# M307A.net
KiCad netlist of a schematic drawn in EAGLE
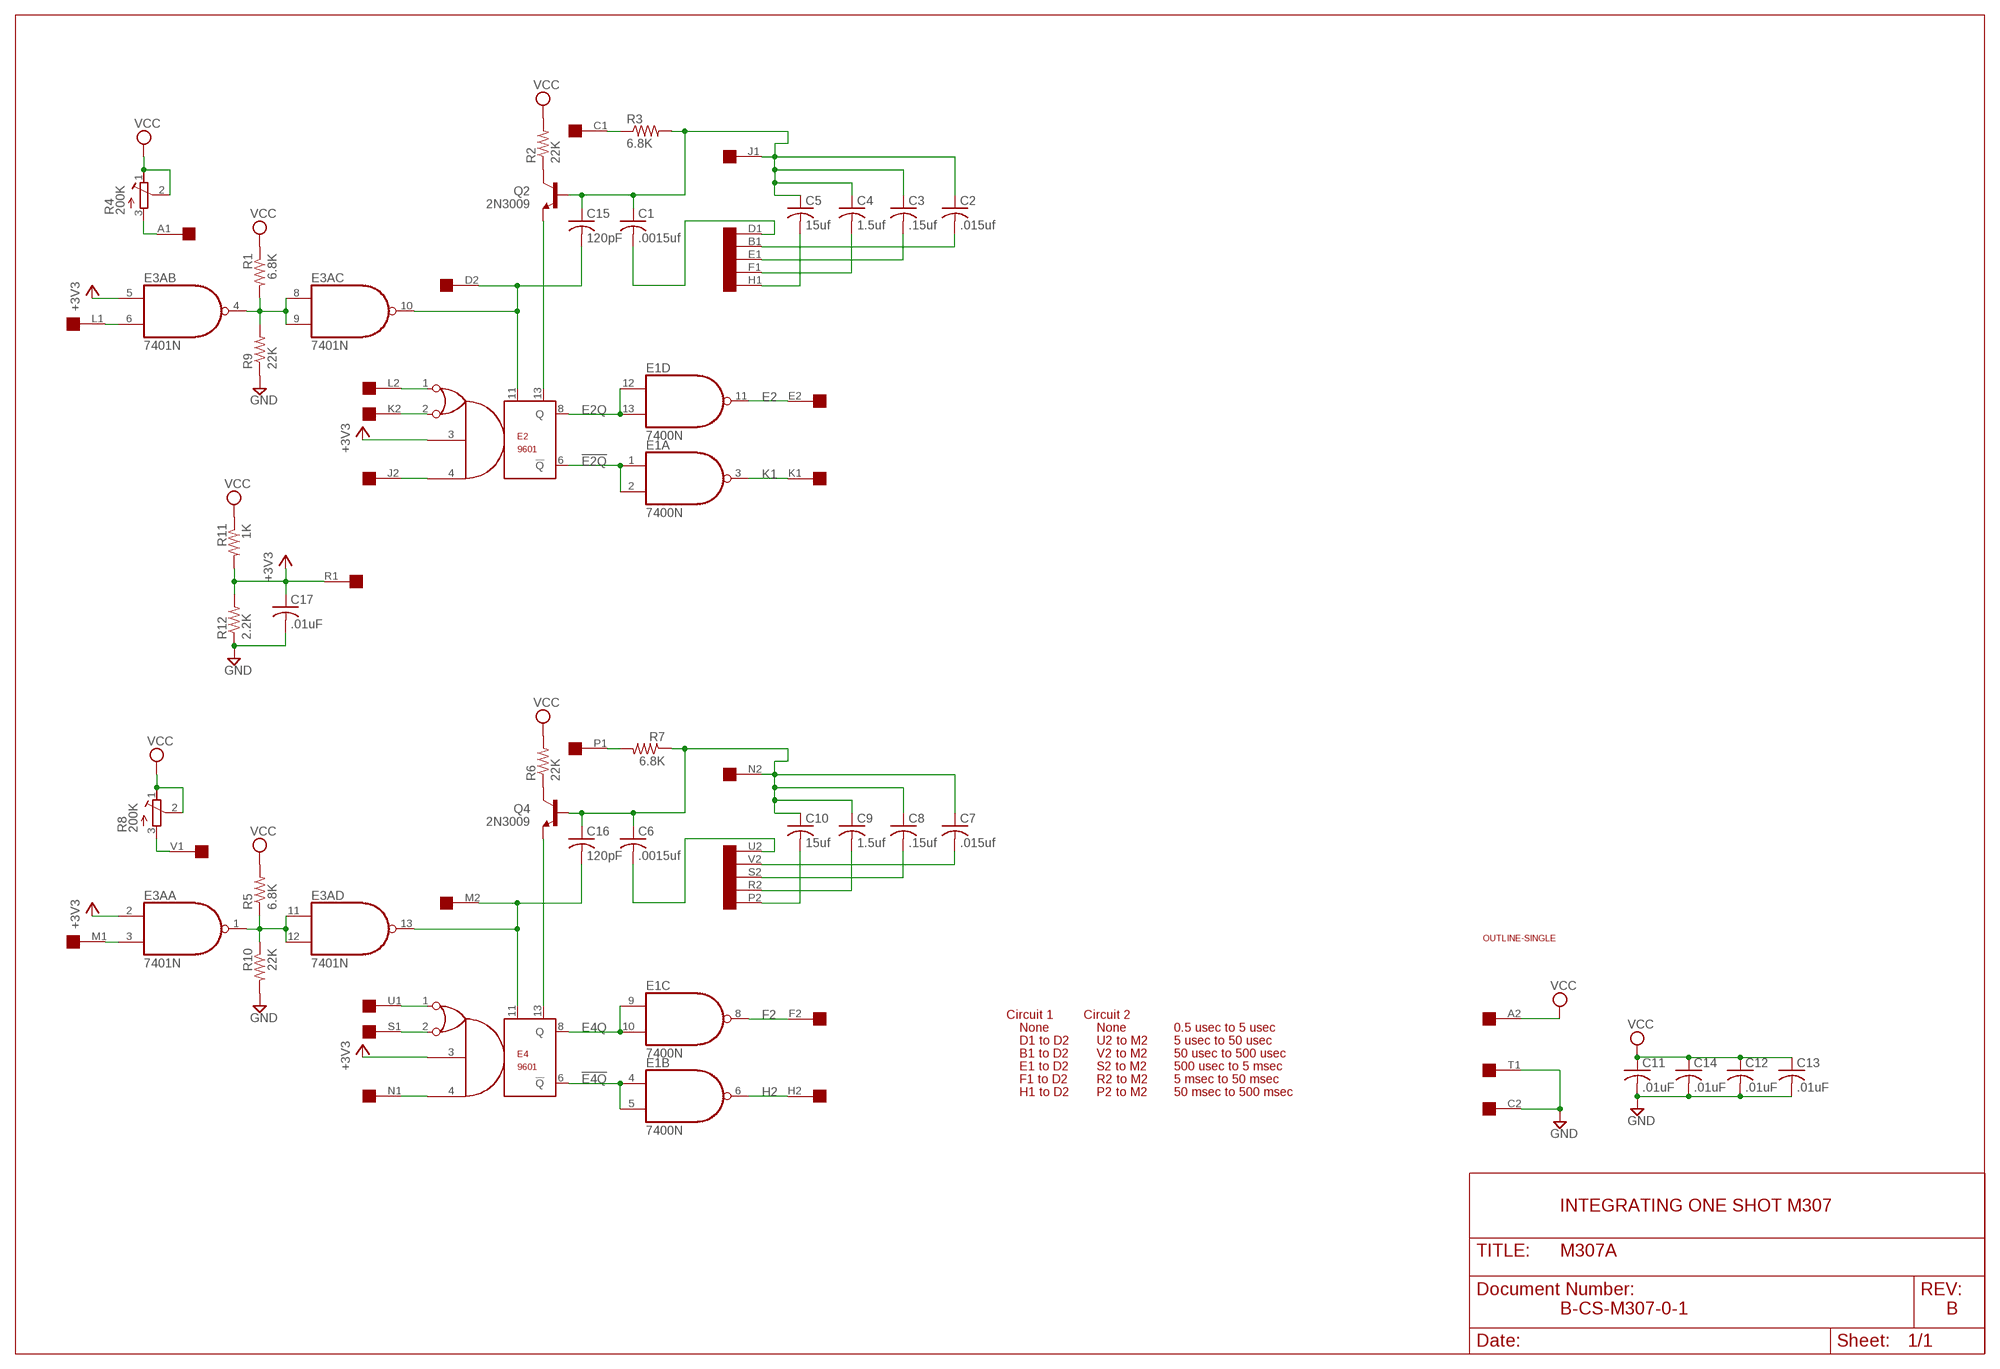
[diagram p0: schematic, sheet 1]

(export (version "E")
  (design (tool "Eeschema 10.0.6"))
  (components
    (comp (ref "C1")
      (value ".0015uf")
      (footprint "eagle-import:C050-025X075")
      (libsource (lib "eagle-import") (part "C-US050-025X075"))
    )
    (comp (ref "C2")
      (value ".015uf")
      (footprint "eagle-import:C150-054X183")
      (libsource (lib "eagle-import") (part "C-US150-054X183"))
    )
    (comp (ref "C3")
      (value ".15uf")
      (footprint "eagle-import:C102-054X133")
      (libsource (lib "eagle-import") (part "C-US102-054X133"))
    )
    (comp (ref "C4")
      (value "1.5uf")
      (footprint "eagle-import:C150-054X183")
      (libsource (lib "eagle-import") (part "C-US150-054X183"))
    )
    (comp (ref "C5")
      (value "15uf")
      (footprint "eagle-import:C150-054X183")
      (libsource (lib "eagle-import") (part "C-US150-054X183"))
    )
    (comp (ref "C6")
      (value ".0015uf")
      (footprint "eagle-import:C050-025X075")
      (libsource (lib "eagle-import") (part "C-US050-025X075"))
    )
    (comp (ref "C7")
      (value ".015uf")
      (footprint "eagle-import:C150-054X183")
      (libsource (lib "eagle-import") (part "C-US150-054X183"))
    )
    (comp (ref "C8")
      (value ".15uf")
      (footprint "eagle-import:C102-054X133")
      (libsource (lib "eagle-import") (part "C-US102-054X133"))
    )
    (comp (ref "C9")
      (value "1.5uf")
      (footprint "eagle-import:C150-054X183")
      (libsource (lib "eagle-import") (part "C-US150-054X183"))
    )
    (comp (ref "C10")
      (value "15uf")
      (footprint "eagle-import:C150-054X183")
      (libsource (lib "eagle-import") (part "C-US150-054X183"))
    )
    (comp (ref "C11")
      (value ".01uF")
      (footprint "eagle-import:C050-025X075")
      (libsource (lib "eagle-import") (part "C-US050-025X075"))
    )
    (comp (ref "C12")
      (value ".01uF")
      (footprint "eagle-import:C050-025X075")
      (libsource (lib "eagle-import") (part "C-US050-025X075"))
    )
    (comp (ref "C13")
      (value ".01uF")
      (footprint "eagle-import:C050-025X075")
      (libsource (lib "eagle-import") (part "C-US050-025X075"))
    )
    (comp (ref "C14")
      (value ".01uF")
      (footprint "eagle-import:C050-025X075")
      (libsource (lib "eagle-import") (part "C-US050-025X075"))
    )
    (comp (ref "C15")
      (value "120pF")
      (footprint "eagle-import:C050-025X075")
      (libsource (lib "eagle-import") (part "C-US050-025X075"))
    )
    (comp (ref "C16")
      (value "120pF")
      (footprint "eagle-import:C050-025X075")
      (libsource (lib "eagle-import") (part "C-US050-025X075"))
    )
    (comp (ref "C17")
      (value ".01uF")
      (footprint "eagle-import:C050-025X075")
      (libsource (lib "eagle-import") (part "C-US050-025X075"))
    )
    (comp (ref "E1")
      (value "7400N")
      (footprint "eagle-import:DIL14")
      (libsource (lib "eagle-import") (part "7400N"))
    )
    (comp (ref "E2")
      (value "9601")
      (footprint "eagle-import:DIL14")
      (libsource (lib "eagle-import") (part "9601"))
    )
    (comp (ref "E3A")
      (value "7401N")
      (footprint "eagle-import:DIL14")
      (libsource (lib "eagle-import") (part "7401NLS"))
    )
    (comp (ref "E4")
      (value "9601")
      (footprint "eagle-import:DIL14")
      (libsource (lib "eagle-import") (part "9601"))
    )
    (comp (ref "Q2")
      (value "2N3009")
      (footprint "eagle-import:TO39")
      (libsource (lib "eagle-import") (part "-NPN-TO39-EBC2N3019"))
    )
    (comp (ref "Q4")
      (value "2N3009")
      (footprint "eagle-import:TO39")
      (libsource (lib "eagle-import") (part "-NPN-TO39-EBC2N3019"))
    )
    (comp (ref "R1")
      (value "6.8K")
      (footprint "eagle-import:0207_10")
      (libsource (lib "eagle-import") (part "R-US_0207/10"))
    )
    (comp (ref "R2")
      (value "22K")
      (footprint "eagle-import:0207_10")
      (libsource (lib "eagle-import") (part "R-US_0207/10"))
    )
    (comp (ref "R3")
      (value "6.8K")
      (footprint "eagle-import:0207_10")
      (libsource (lib "eagle-import") (part "R-US_0207/10"))
    )
    (comp (ref "R4")
      (value "200K")
      (footprint "eagle-import:3006Y")
      (libsource (lib "eagle-import") (part "275P"))
    )
    (comp (ref "R5")
      (value "6.8K")
      (footprint "eagle-import:0207_10")
      (libsource (lib "eagle-import") (part "R-US_0207/10"))
    )
    (comp (ref "R6")
      (value "22K")
      (footprint "eagle-import:0207_10")
      (libsource (lib "eagle-import") (part "R-US_0207/10"))
    )
    (comp (ref "R7")
      (value "6.8K")
      (footprint "eagle-import:0207_10")
      (libsource (lib "eagle-import") (part "R-US_0207/10"))
    )
    (comp (ref "R8")
      (value "200K")
      (footprint "eagle-import:3006Y")
      (libsource (lib "eagle-import") (part "275P"))
    )
    (comp (ref "R9")
      (value "22K")
      (footprint "eagle-import:0207_10")
      (libsource (lib "eagle-import") (part "R-US_0207/10"))
    )
    (comp (ref "R10")
      (value "22K")
      (footprint "eagle-import:0207_10")
      (libsource (lib "eagle-import") (part "R-US_0207/10"))
    )
    (comp (ref "R11")
      (value "1K")
      (footprint "eagle-import:0207_10")
      (libsource (lib "eagle-import") (part "R-US_0207/10"))
    )
    (comp (ref "R12")
      (value "2.2K")
      (footprint "eagle-import:0207_10")
      (libsource (lib "eagle-import") (part "R-US_0207/10"))
    )
    (comp (ref "U$1")
      (value "OUTLINE-SINGLE")
      (footprint "eagle-import:SINGLE")
      (libsource (lib "eagle-import") (part "OUTLINE-SINGLE"))
    )
    (comp (ref "U$4")
      (value "SINGLE")
      (footprint "eagle-import:EDGE-CON2")
      (libsource (lib "eagle-import") (part "SINGLE"))
    )
  )
  (nets
    (net (code "1") (name "+3V3") (class "Default")
      (node (ref "C17") (pin "1") (pinfunction "1_1") (pintype "passive"))
      (node (ref "E2") (pin "3") (pinfunction "P$3_3") (pintype "input"))
      (node (ref "E3A") (pin "2") (pinfunction "I0_2") (pintype "input"))
      (node (ref "E3A") (pin "5") (pinfunction "I0_5") (pintype "input"))
      (node (ref "E4") (pin "3") (pinfunction "P$3_3") (pintype "input"))
      (node (ref "R11") (pin "2") (pinfunction "2_2") (pintype "passive"))
      (node (ref "R12") (pin "2") (pinfunction "2_2") (pintype "passive"))
      (node (ref "U$4") (pin "R1") (pinfunction "1_R1") (pintype "bidirectional"))
    )
    (net (code "2") (name "/E2") (class "Default")
      (node (ref "E1") (pin "11") (pinfunction "O_11") (pintype "output"))
      (node (ref "U$4") (pin "E2") (pinfunction "1_E2") (pintype "bidirectional"))
    )
    (net (code "3") (name "/E2Q") (class "Default")
      (node (ref "E1") (pin "12") (pinfunction "I0_12") (pintype "input"))
      (node (ref "E1") (pin "13") (pinfunction "I1_13") (pintype "input"))
      (node (ref "E2") (pin "8") (pinfunction "Q_8") (pintype "output"))
    )
    (net (code "4") (name "/E4Q") (class "Default")
      (node (ref "E1") (pin "10") (pinfunction "I1_10") (pintype "input"))
      (node (ref "E1") (pin "9") (pinfunction "I0_9") (pintype "input"))
      (node (ref "E4") (pin "8") (pinfunction "Q_8") (pintype "output"))
    )
    (net (code "5") (name "/F2") (class "Default")
      (node (ref "E1") (pin "8") (pinfunction "O_8") (pintype "output"))
      (node (ref "U$4") (pin "F2") (pinfunction "1_F2") (pintype "bidirectional"))
    )
    (net (code "6") (name "/H2") (class "Default")
      (node (ref "E1") (pin "6") (pinfunction "O_6") (pintype "output"))
      (node (ref "U$4") (pin "H2") (pinfunction "1_H2") (pintype "bidirectional"))
    )
    (net (code "7") (name "/K1") (class "Default")
      (node (ref "E1") (pin "3") (pinfunction "O_3") (pintype "output"))
      (node (ref "U$4") (pin "K1") (pinfunction "1_K1") (pintype "bidirectional"))
    )
    (net (code "8") (name "/~{E2Q}") (class "Default")
      (node (ref "E1") (pin "1") (pinfunction "I0_1") (pintype "input"))
      (node (ref "E1") (pin "2") (pinfunction "I1_2") (pintype "input"))
      (node (ref "E2") (pin "6") (pinfunction "~{Q}_6") (pintype "output"))
    )
    (net (code "9") (name "/~{E4Q}") (class "Default")
      (node (ref "E1") (pin "4") (pinfunction "I0_4") (pintype "input"))
      (node (ref "E1") (pin "5") (pinfunction "I1_5") (pintype "input"))
      (node (ref "E4") (pin "6") (pinfunction "~{Q}_6") (pintype "output"))
    )
    (net (code "10") (name "GND") (class "Default")
      (node (ref "C11") (pin "2") (pinfunction "2_2") (pintype "passive"))
      (node (ref "C12") (pin "2") (pinfunction "2_2") (pintype "passive"))
      (node (ref "C13") (pin "2") (pinfunction "2_2") (pintype "passive"))
      (node (ref "C14") (pin "2") (pinfunction "2_2") (pintype "passive"))
      (node (ref "C17") (pin "2") (pinfunction "2_2") (pintype "passive"))
      (node (ref "R10") (pin "2") (pinfunction "2_2") (pintype "passive"))
      (node (ref "R12") (pin "1") (pinfunction "1_1") (pintype "passive"))
      (node (ref "R9") (pin "1") (pinfunction "1_1") (pintype "passive"))
      (node (ref "U$4") (pin "C2") (pinfunction "1_C2") (pintype "bidirectional"))
      (node (ref "U$4") (pin "T1") (pinfunction "1_T1") (pintype "bidirectional"))
    )
    (net (code "11") (name "Net-(E2A-P$1)") (class "Default")
      (node (ref "E2") (pin "1") (pinfunction "P$1_1") (pintype "input"))
      (node (ref "U$4") (pin "L2") (pinfunction "1_L2") (pintype "bidirectional"))
    )
    (net (code "12") (name "Net-(E2A-P$2)") (class "Default")
      (node (ref "E2") (pin "2") (pinfunction "P$2_2") (pintype "input"))
      (node (ref "U$4") (pin "K2") (pinfunction "1_K2") (pintype "bidirectional"))
    )
    (net (code "13") (name "Net-(E2A-P$4)") (class "Default")
      (node (ref "E2") (pin "4") (pinfunction "P$4_4") (pintype "input"))
      (node (ref "U$4") (pin "J2") (pinfunction "1_J2") (pintype "bidirectional"))
    )
    (net (code "14") (name "Net-(E2A-P$5)") (class "Default")
      (node (ref "C15") (pin "2") (pinfunction "2_2") (pintype "passive"))
      (node (ref "E2") (pin "11") (pinfunction "P$5_11") (pintype "bidirectional"))
      (node (ref "E3A") (pin "10") (pinfunction "O_10") (pintype "open_collector"))
      (node (ref "U$4") (pin "D2") (pinfunction "1_D2") (pintype "bidirectional"))
    )
    (net (code "15") (name "Net-(E2A-P$6)") (class "Default")
      (node (ref "E2") (pin "13") (pinfunction "P$6_13") (pintype "bidirectional"))
      (node (ref "Q2") (pin "1") (pinfunction "E_1") (pintype "passive"))
    )
    (net (code "16") (name "Net-(E3AA-I1)") (class "Default")
      (node (ref "E3A") (pin "3") (pinfunction "I1_3") (pintype "input"))
      (node (ref "U$4") (pin "M1") (pinfunction "1_M1") (pintype "bidirectional"))
    )
    (net (code "17") (name "Net-(E3AA-O)") (class "Default")
      (node (ref "E3A") (pin "1") (pinfunction "O_1") (pintype "open_collector"))
      (node (ref "E3A") (pin "11") (pinfunction "I0_11") (pintype "input"))
      (node (ref "E3A") (pin "12") (pinfunction "I1_12") (pintype "input"))
      (node (ref "R10") (pin "1") (pinfunction "1_1") (pintype "passive"))
      (node (ref "R5") (pin "1") (pinfunction "1_1") (pintype "passive"))
    )
    (net (code "18") (name "Net-(E3AB-I1)") (class "Default")
      (node (ref "E3A") (pin "6") (pinfunction "I1_6") (pintype "input"))
      (node (ref "U$4") (pin "L1") (pinfunction "1_L1") (pintype "bidirectional"))
    )
    (net (code "19") (name "Net-(E3AB-O)") (class "Default")
      (node (ref "E3A") (pin "4") (pinfunction "O_4") (pintype "open_collector"))
      (node (ref "E3A") (pin "8") (pinfunction "I0_8") (pintype "input"))
      (node (ref "E3A") (pin "9") (pinfunction "I1_9") (pintype "input"))
      (node (ref "R1") (pin "2") (pinfunction "2_2") (pintype "passive"))
      (node (ref "R9") (pin "2") (pinfunction "2_2") (pintype "passive"))
    )
    (net (code "20") (name "Net-(E3AD-O)") (class "Default")
      (node (ref "C16") (pin "2") (pinfunction "2_2") (pintype "passive"))
      (node (ref "E3A") (pin "13") (pinfunction "O_13") (pintype "open_collector"))
      (node (ref "E4") (pin "11") (pinfunction "P$5_11") (pintype "bidirectional"))
      (node (ref "U$4") (pin "M2") (pinfunction "1_M2") (pintype "bidirectional"))
    )
    (net (code "21") (name "Net-(E4A-P$1)") (class "Default")
      (node (ref "E4") (pin "1") (pinfunction "P$1_1") (pintype "input"))
      (node (ref "U$4") (pin "U1") (pinfunction "1_U1") (pintype "bidirectional"))
    )
    (net (code "22") (name "Net-(E4A-P$2)") (class "Default")
      (node (ref "E4") (pin "2") (pinfunction "P$2_2") (pintype "input"))
      (node (ref "U$4") (pin "S1") (pinfunction "1_S1") (pintype "bidirectional"))
    )
    (net (code "23") (name "Net-(E4A-P$4)") (class "Default")
      (node (ref "E4") (pin "4") (pinfunction "P$4_4") (pintype "input"))
      (node (ref "U$4") (pin "N1") (pinfunction "1_N1") (pintype "bidirectional"))
    )
    (net (code "24") (name "Net-(E4A-P$6)") (class "Default")
      (node (ref "E4") (pin "13") (pinfunction "P$6_13") (pintype "bidirectional"))
      (node (ref "Q4") (pin "1") (pinfunction "E_1") (pintype "passive"))
    )
    (net (code "25") (name "Net-(Q2-B)") (class "Default")
      (node (ref "C1") (pin "1") (pinfunction "1_1") (pintype "passive"))
      (node (ref "C15") (pin "1") (pinfunction "1_1") (pintype "passive"))
      (node (ref "C2") (pin "1") (pinfunction "1_1") (pintype "passive"))
      (node (ref "C3") (pin "1") (pinfunction "1_1") (pintype "passive"))
      (node (ref "C4") (pin "1") (pinfunction "1_1") (pintype "passive"))
      (node (ref "C5") (pin "1") (pinfunction "1_1") (pintype "passive"))
      (node (ref "Q2") (pin "2") (pinfunction "B_2") (pintype "passive"))
      (node (ref "R3") (pin "2") (pinfunction "2_2") (pintype "passive"))
      (node (ref "U$4") (pin "J1") (pinfunction "1_J1") (pintype "bidirectional"))
    )
    (net (code "26") (name "Net-(Q2-C)") (class "Default")
      (node (ref "Q2") (pin "3") (pinfunction "C_3") (pintype "passive"))
      (node (ref "R2") (pin "1") (pinfunction "1_1") (pintype "passive"))
    )
    (net (code "27") (name "Net-(Q4-B)") (class "Default")
      (node (ref "C10") (pin "1") (pinfunction "1_1") (pintype "passive"))
      (node (ref "C16") (pin "1") (pinfunction "1_1") (pintype "passive"))
      (node (ref "C6") (pin "1") (pinfunction "1_1") (pintype "passive"))
      (node (ref "C7") (pin "1") (pinfunction "1_1") (pintype "passive"))
      (node (ref "C8") (pin "1") (pinfunction "1_1") (pintype "passive"))
      (node (ref "C9") (pin "1") (pinfunction "1_1") (pintype "passive"))
      (node (ref "Q4") (pin "2") (pinfunction "B_2") (pintype "passive"))
      (node (ref "R7") (pin "1") (pinfunction "1_1") (pintype "passive"))
      (node (ref "U$4") (pin "N2") (pinfunction "1_N2") (pintype "bidirectional"))
    )
    (net (code "28") (name "Net-(Q4-C)") (class "Default")
      (node (ref "Q4") (pin "3") (pinfunction "C_3") (pintype "passive"))
      (node (ref "R6") (pin "1") (pinfunction "1_1") (pintype "passive"))
    )
    (net (code "29") (name "Net-(R4-E)") (class "Default")
      (node (ref "R4") (pin "3") (pinfunction "E_3") (pintype "passive"))
      (node (ref "U$4") (pin "A1") (pinfunction "1_A1") (pintype "bidirectional"))
    )
    (net (code "30") (name "Net-(R8-E)") (class "Default")
      (node (ref "R8") (pin "3") (pinfunction "E_3") (pintype "passive"))
      (node (ref "U$4") (pin "V1") (pinfunction "1_V1") (pintype "bidirectional"))
    )
    (net (code "31") (name "Net-(U$4AB-1)") (class "Default")
      (node (ref "C9") (pin "2") (pinfunction "2_2") (pintype "passive"))
      (node (ref "U$4") (pin "R2") (pinfunction "1_R2") (pintype "bidirectional"))
    )
    (net (code "32") (name "Net-(U$4AD-1)") (class "Default")
      (node (ref "C8") (pin "2") (pinfunction "2_2") (pintype "passive"))
      (node (ref "U$4") (pin "S2") (pinfunction "1_S2") (pintype "bidirectional"))
    )
    (net (code "33") (name "Net-(U$4AH-1)") (class "Default")
      (node (ref "C6") (pin "2") (pinfunction "2_2") (pintype "passive"))
      (node (ref "U$4") (pin "U2") (pinfunction "1_U2") (pintype "bidirectional"))
    )
    (net (code "34") (name "Net-(U$4AJ-1)") (class "Default")
      (node (ref "C7") (pin "2") (pinfunction "2_2") (pintype "passive"))
      (node (ref "U$4") (pin "V2") (pinfunction "1_V2") (pintype "bidirectional"))
    )
    (net (code "35") (name "Net-(U$4C-1)") (class "Default")
      (node (ref "C2") (pin "2") (pinfunction "2_2") (pintype "passive"))
      (node (ref "U$4") (pin "B1") (pinfunction "1_B1") (pintype "bidirectional"))
    )
    (net (code "36") (name "Net-(U$4E-1)") (class "Default")
      (node (ref "R3") (pin "1") (pinfunction "1_1") (pintype "passive"))
      (node (ref "U$4") (pin "C1") (pinfunction "1_C1") (pintype "bidirectional"))
    )
    (net (code "37") (name "Net-(U$4G-1)") (class "Default")
      (node (ref "C1") (pin "2") (pinfunction "2_2") (pintype "passive"))
      (node (ref "U$4") (pin "D1") (pinfunction "1_D1") (pintype "bidirectional"))
    )
    (net (code "38") (name "Net-(U$4I-1)") (class "Default")
      (node (ref "C3") (pin "2") (pinfunction "2_2") (pintype "passive"))
      (node (ref "U$4") (pin "E1") (pinfunction "1_E1") (pintype "bidirectional"))
    )
    (net (code "39") (name "Net-(U$4K-1)") (class "Default")
      (node (ref "C4") (pin "2") (pinfunction "2_2") (pintype "passive"))
      (node (ref "U$4") (pin "F1") (pinfunction "1_F1") (pintype "bidirectional"))
    )
    (net (code "40") (name "Net-(U$4M-1)") (class "Default")
      (node (ref "C5") (pin "2") (pinfunction "2_2") (pintype "passive"))
      (node (ref "U$4") (pin "H1") (pinfunction "1_H1") (pintype "bidirectional"))
    )
    (net (code "41") (name "Net-(U$4Y-1)") (class "Default")
      (node (ref "R7") (pin "2") (pinfunction "2_2") (pintype "passive"))
      (node (ref "U$4") (pin "P1") (pinfunction "1_P1") (pintype "bidirectional"))
    )
    (net (code "42") (name "Net-(U$4Z-1)") (class "Default")
      (node (ref "C10") (pin "2") (pinfunction "2_2") (pintype "passive"))
      (node (ref "U$4") (pin "P2") (pinfunction "1_P2") (pintype "bidirectional"))
    )
    (net (code "43") (name "VCC") (class "Default")
      (node (ref "C11") (pin "1") (pinfunction "1_1") (pintype "passive"))
      (node (ref "C12") (pin "1") (pinfunction "1_1") (pintype "passive"))
      (node (ref "C13") (pin "1") (pinfunction "1_1") (pintype "passive"))
      (node (ref "C14") (pin "1") (pinfunction "1_1") (pintype "passive"))
      (node (ref "R1") (pin "1") (pinfunction "1_1") (pintype "passive"))
      (node (ref "R11") (pin "1") (pinfunction "1_1") (pintype "passive"))
      (node (ref "R2") (pin "2") (pinfunction "2_2") (pintype "passive"))
      (node (ref "R4") (pin "1") (pinfunction "A_1") (pintype "passive"))
      (node (ref "R4") (pin "2") (pinfunction "S_2") (pintype "passive"))
      (node (ref "R5") (pin "2") (pinfunction "2_2") (pintype "passive"))
      (node (ref "R6") (pin "2") (pinfunction "2_2") (pintype "passive"))
      (node (ref "R8") (pin "1") (pinfunction "A_1") (pintype "passive"))
      (node (ref "R8") (pin "2") (pinfunction "S_2") (pintype "passive"))
      (node (ref "U$4") (pin "A2") (pinfunction "1_A2") (pintype "bidirectional"))
    )
  )
)
